# Remote_8-bit_I2C.net
KiCad netlist of a schematic drawn in Altium Designer
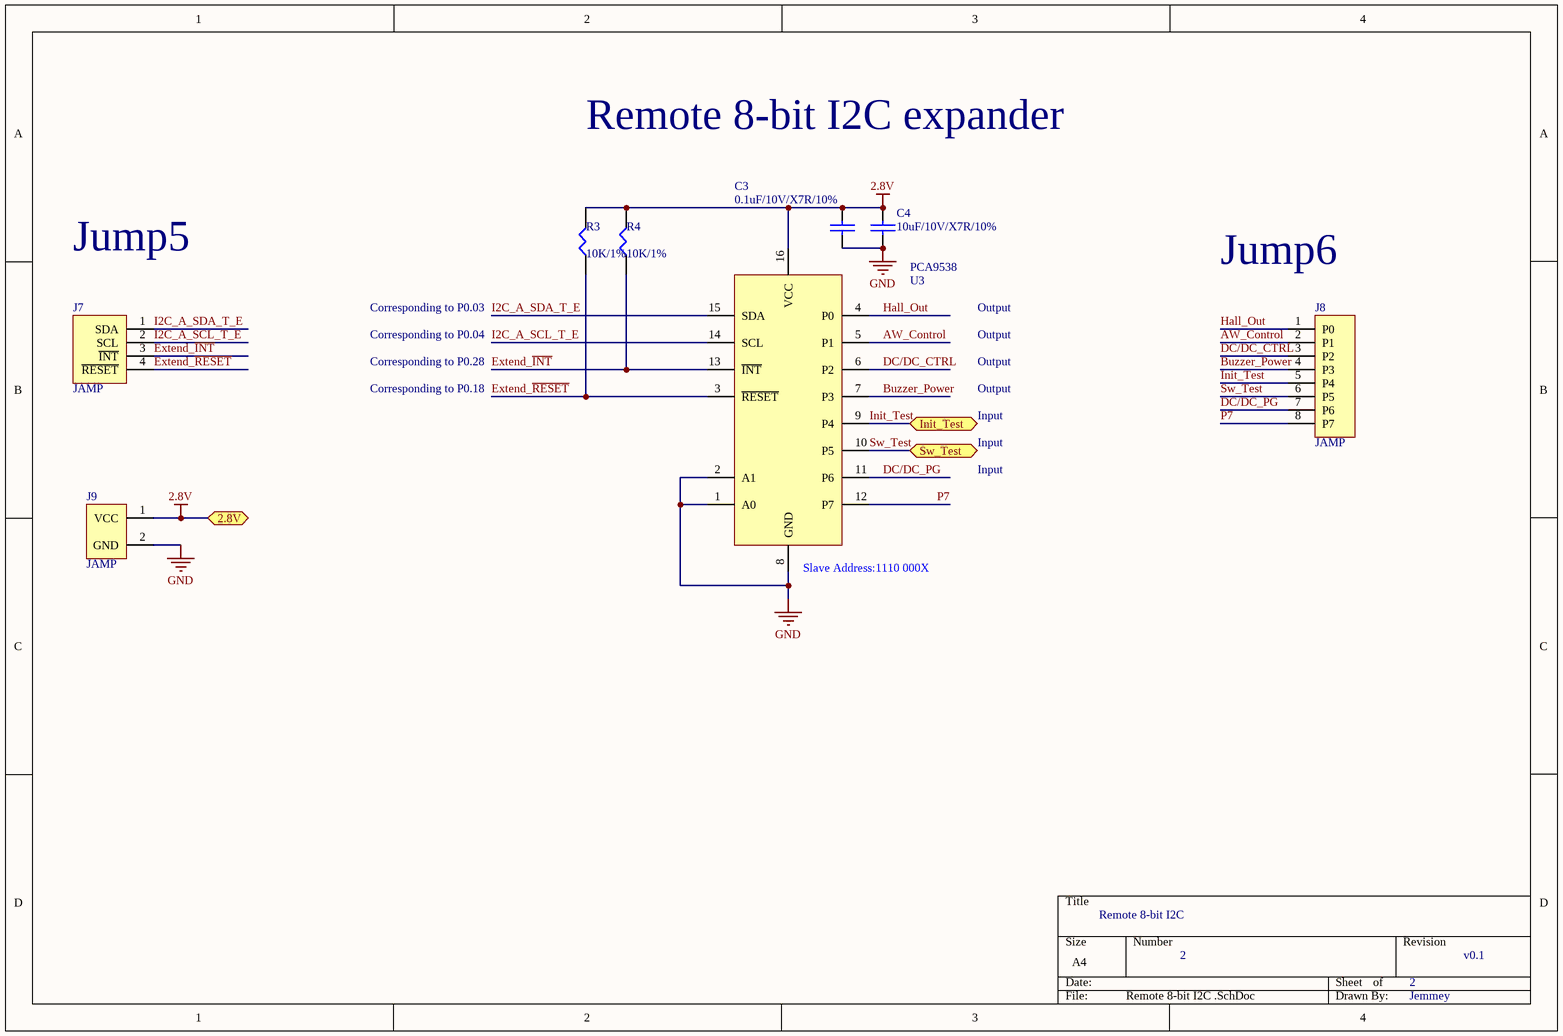
[diagram p0: Remote 8-bit I2C .SchDoc]

(export (version "E")
  (design (tool "Eeschema 10.0.6"))
  (components
    (comp (ref "C3")
      (value "0.1uF/10V/X7R/10%")
      (footprint "0402C")
      (description "厂家：Murata，型号：GRM155R71A104KA01D")
      (libsource (lib "*") (part "CAP"))
    )
    (comp (ref "C4")
      (value "10uF/10V/X7R/10%")
      (footprint "0603C")
      (description "厂家：Murata，型号：GRM188R61A106KE69D")
      (libsource (lib "*") (part "CAP"))
    )
    (comp (ref "J7")
      (value "JAMP")
      (footprint "Debug- 1.27*4")
      (description "厂家：暂定，型号：暂定")
      (libsource (lib "Step Moter Control") (part "JAMP"))
    )
    (comp (ref "J8")
      (value "JAMP")
      (footprint "Debug- 1.27*8")
      (description "厂家：暂定，型号：暂定")
      (libsource (lib "") (part "JAMP_2"))
    )
    (comp (ref "J9")
      (value "JAMP")
      (footprint "Debug- 1.27*2")
      (description "厂家：暂定，型号：暂定")
      (libsource (lib "") (part "JAMP_1"))
    )
    (comp (ref "R3")
      (value "10K/1%")
      (footprint "0402R")
      (description "厂家：Yageo，型号：RC0402FR-0710KL")
      (libsource (lib "*") (part "RES1"))
    )
    (comp (ref "R4")
      (value "10K/1%")
      (footprint "0402R")
      (description "厂家：Yageo，型号：RC0402FR-0710KL")
      (libsource (lib "*") (part "RES1"))
    )
    (comp (ref "U3")
      (value "PCA9538")
      (footprint "TSSOP-16")
      (description "厂家：TI，型号：PCA9538 Remote 8-bit I2C with interrupt output")
      (libsource (lib "Step Moter Control") (part "PCA9538"))
    )
  )
  (nets
    (net (code "1") (name "/AW_Control") (class "Default")
      (node (ref "J8") (pin "2") (pinfunction "P1_2") (pintype "passive"))
      (node (ref "U3") (pin "5") (pinfunction "P1_5") (pintype "passive"))
    )
    (net (code "2") (name "/Buzzer_Power") (class "Default")
      (node (ref "J8") (pin "4") (pinfunction "P3_4") (pintype "passive"))
      (node (ref "U3") (pin "7") (pinfunction "P3_7") (pintype "passive"))
    )
    (net (code "3") (name "/DC{slash}DC_CTRL") (class "Default")
      (node (ref "J8") (pin "3") (pinfunction "P2_3") (pintype "passive"))
      (node (ref "U3") (pin "6") (pinfunction "P2_6") (pintype "passive"))
    )
    (net (code "4") (name "/DC{slash}DC_PG") (class "Default")
      (node (ref "J8") (pin "7") (pinfunction "P6_7") (pintype "passive"))
      (node (ref "U3") (pin "11") (pinfunction "P6_11") (pintype "passive"))
    )
    (net (code "5") (name "/Extend_~{INT}") (class "Default")
      (node (ref "J7") (pin "3") (pinfunction "~{INT}_3") (pintype "passive"))
      (node (ref "R4") (pin "1") (pinfunction "1_1") (pintype "passive"))
      (node (ref "U3") (pin "13") (pinfunction "~{INT}_13") (pintype "passive"))
    )
    (net (code "6") (name "/Extend_~{RESET}") (class "Default")
      (node (ref "J7") (pin "4") (pinfunction "~{RESET}_4") (pintype "passive"))
      (node (ref "R3") (pin "1") (pinfunction "1_1") (pintype "passive"))
      (node (ref "U3") (pin "3") (pinfunction "~{RESET}_3") (pintype "passive"))
    )
    (net (code "7") (name "/Hall_Out") (class "Default")
      (node (ref "J8") (pin "1") (pinfunction "P0_1") (pintype "passive"))
      (node (ref "U3") (pin "4") (pinfunction "P0_4") (pintype "passive"))
    )
    (net (code "8") (name "/I2C_A_SCL_T_E") (class "Default")
      (node (ref "J7") (pin "2") (pinfunction "SCL_2") (pintype "passive"))
      (node (ref "U3") (pin "14") (pinfunction "SCL_14") (pintype "passive"))
    )
    (net (code "9") (name "/I2C_A_SDA_T_E") (class "Default")
      (node (ref "J7") (pin "1") (pinfunction "SDA_1") (pintype "passive"))
      (node (ref "U3") (pin "15") (pinfunction "SDA_15") (pintype "passive"))
    )
    (net (code "10") (name "/Init_Test") (class "Default")
      (node (ref "J8") (pin "5") (pinfunction "P4_5") (pintype "passive"))
      (node (ref "U3") (pin "9") (pinfunction "P4_9") (pintype "passive"))
    )
    (net (code "11") (name "/P7") (class "Default")
      (node (ref "J8") (pin "8") (pinfunction "P7_8") (pintype "passive"))
      (node (ref "U3") (pin "12") (pinfunction "P7_12") (pintype "passive"))
    )
    (net (code "12") (name "/Sw_Test") (class "Default")
      (node (ref "J8") (pin "6") (pinfunction "P5_6") (pintype "passive"))
      (node (ref "U3") (pin "10") (pinfunction "P5_10") (pintype "passive"))
    )
    (net (code "13") (name "2.8V") (class "Default")
      (node (ref "C3") (pin "1") (pinfunction "1_1") (pintype "passive"))
      (node (ref "C4") (pin "1") (pinfunction "1_1") (pintype "passive"))
      (node (ref "J9") (pin "1") (pinfunction "VCC_1") (pintype "passive"))
      (node (ref "R3") (pin "2") (pinfunction "2_2") (pintype "passive"))
      (node (ref "R4") (pin "2") (pinfunction "2_2") (pintype "passive"))
      (node (ref "U3") (pin "16") (pinfunction "VCC_16") (pintype "passive"))
    )
    (net (code "14") (name "GND") (class "Default")
      (node (ref "C3") (pin "2") (pinfunction "2_2") (pintype "passive"))
      (node (ref "C4") (pin "2") (pinfunction "2_2") (pintype "passive"))
      (node (ref "J9") (pin "2") (pinfunction "GND_2") (pintype "passive"))
      (node (ref "U3") (pin "1") (pinfunction "A0_1") (pintype "passive"))
      (node (ref "U3") (pin "2") (pinfunction "A1_2") (pintype "passive"))
      (node (ref "U3") (pin "8") (pinfunction "GND_8") (pintype "passive"))
    )
  )
)
